# FMC_HPC_UFL_DEBUG_TP_SMA.net
KiCad netlist of a schematic drawn in Altium Designer
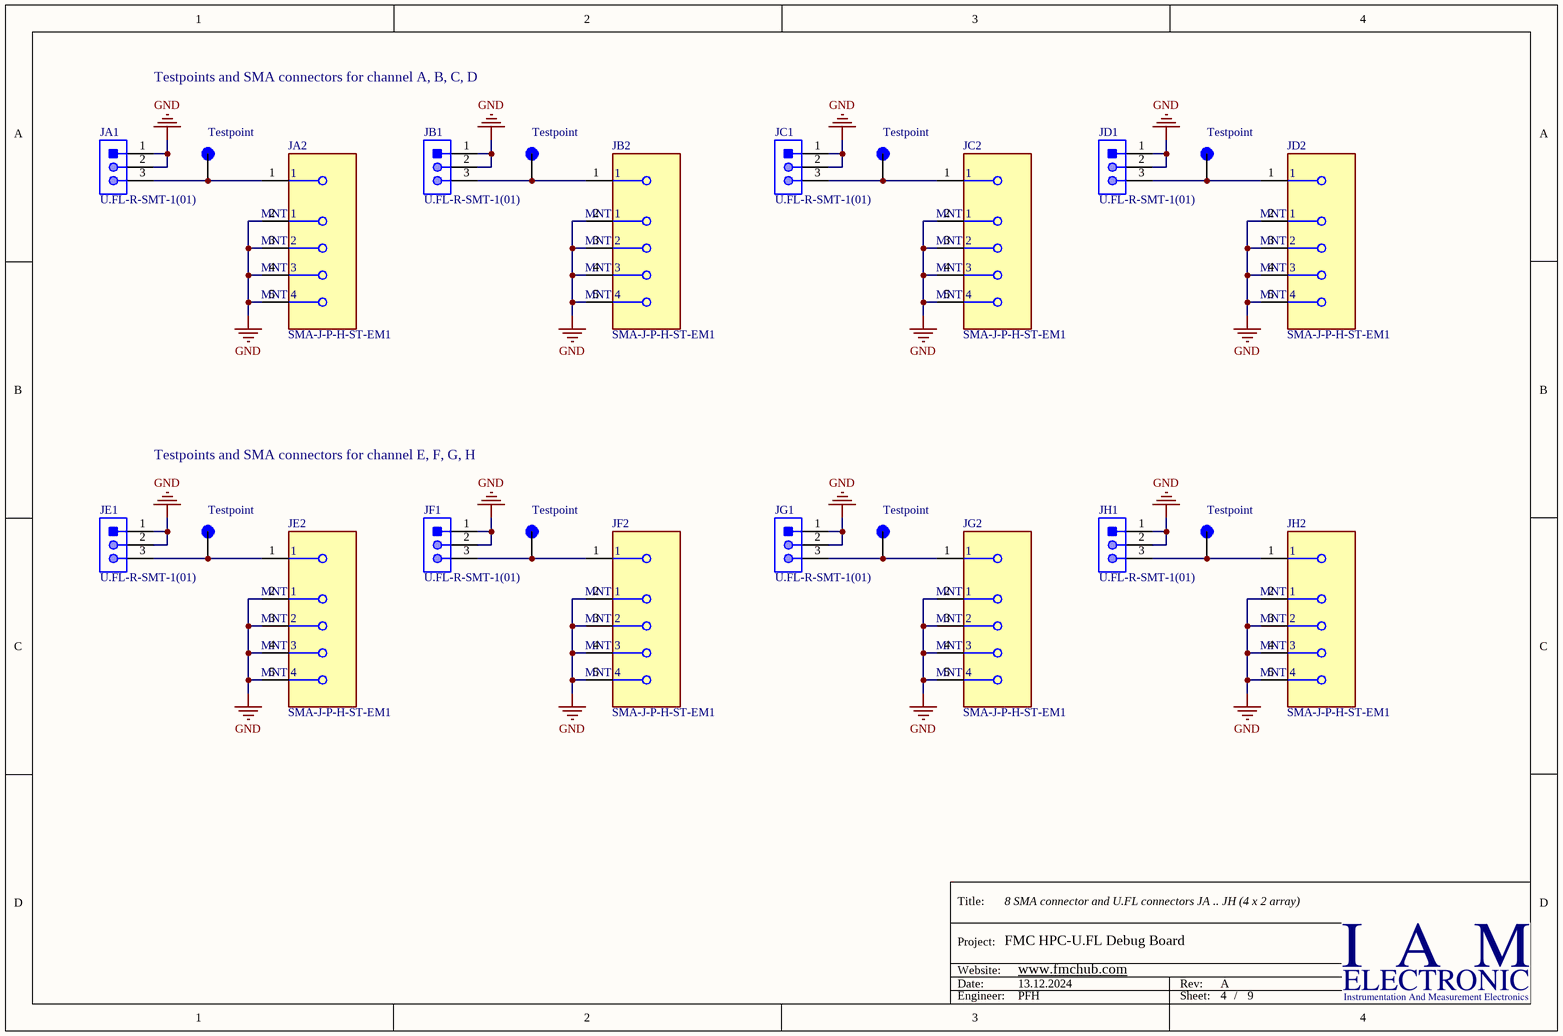
[diagram p0: FMC_HPC_UFL_DEBUG_TP_SMA.SchDoc]

(export (version "E")
  (design (tool "Eeschema 10.0.6"))
  (components
    (comp (ref "JA1")
      (value "U.FL-R-SMT-1(01)")
      (footprint "HRS-U.FL-R-SMT-3_V")
      (description "Ultra Small Coaxial Connector, 6 GHz, -40 to 90 degC, 3-Pin SMD, RoHS, Bulk")
      (fields (field (name "MANUFACTURER") "Hirose Electric"))
      (libsource (lib "Altium Content Vault") (part "CN-1P-M-R3"))
    )
    (comp (ref "JA2")
      (value "SMA-J-P-H-ST-EM1")
      (footprint "FP-SMA-J-P-H-ST-EM1-MFG")
      (description "CONN SMA JACK STR 50OHM EDGE MNT")
      (fields (field (name "MANUFACTURER") "Samtec"))
      (libsource (lib "Altium Content Vault") (part "c65b8a639cdaef1819ea20b5466f8fa"))
    )
    (comp (ref "JB1")
      (value "U.FL-R-SMT-1(01)")
      (footprint "HRS-U.FL-R-SMT-3_V")
      (description "Ultra Small Coaxial Connector, 6 GHz, -40 to 90 degC, 3-Pin SMD, RoHS, Bulk")
      (fields (field (name "MANUFACTURER") "Hirose Electric"))
      (libsource (lib "Altium Content Vault") (part "CN-1P-M-R3"))
    )
    (comp (ref "JB2")
      (value "SMA-J-P-H-ST-EM1")
      (footprint "FP-SMA-J-P-H-ST-EM1-MFG")
      (description "CONN SMA JACK STR 50OHM EDGE MNT")
      (fields (field (name "MANUFACTURER") "Samtec"))
      (libsource (lib "Altium Content Vault") (part "c65b8a639cdaef1819ea20b5466f8fa"))
    )
    (comp (ref "JC1")
      (value "U.FL-R-SMT-1(01)")
      (footprint "HRS-U.FL-R-SMT-3_V")
      (description "Ultra Small Coaxial Connector, 6 GHz, -40 to 90 degC, 3-Pin SMD, RoHS, Bulk")
      (fields (field (name "MANUFACTURER") "Hirose Electric"))
      (libsource (lib "Altium Content Vault") (part "CN-1P-M-R3"))
    )
    (comp (ref "JC2")
      (value "SMA-J-P-H-ST-EM1")
      (footprint "FP-SMA-J-P-H-ST-EM1-MFG")
      (description "CONN SMA JACK STR 50OHM EDGE MNT")
      (fields (field (name "MANUFACTURER") "Samtec"))
      (libsource (lib "Altium Content Vault") (part "c65b8a639cdaef1819ea20b5466f8fa"))
    )
    (comp (ref "JD1")
      (value "U.FL-R-SMT-1(01)")
      (footprint "HRS-U.FL-R-SMT-3_V")
      (description "Ultra Small Coaxial Connector, 6 GHz, -40 to 90 degC, 3-Pin SMD, RoHS, Bulk")
      (fields (field (name "MANUFACTURER") "Hirose Electric"))
      (libsource (lib "Altium Content Vault") (part "CN-1P-M-R3"))
    )
    (comp (ref "JD2")
      (value "SMA-J-P-H-ST-EM1")
      (footprint "FP-SMA-J-P-H-ST-EM1-MFG")
      (description "CONN SMA JACK STR 50OHM EDGE MNT")
      (fields (field (name "MANUFACTURER") "Samtec"))
      (libsource (lib "Altium Content Vault") (part "c65b8a639cdaef1819ea20b5466f8fa"))
    )
    (comp (ref "JE1")
      (value "U.FL-R-SMT-1(01)")
      (footprint "HRS-U.FL-R-SMT-3_V")
      (description "Ultra Small Coaxial Connector, 6 GHz, -40 to 90 degC, 3-Pin SMD, RoHS, Bulk")
      (fields (field (name "MANUFACTURER") "Hirose Electric"))
      (libsource (lib "Altium Content Vault") (part "CN-1P-M-R3"))
    )
    (comp (ref "JE2")
      (value "SMA-J-P-H-ST-EM1")
      (footprint "FP-SMA-J-P-H-ST-EM1-MFG")
      (description "CONN SMA JACK STR 50OHM EDGE MNT")
      (fields (field (name "MANUFACTURER") "Samtec"))
      (libsource (lib "Altium Content Vault") (part "c65b8a639cdaef1819ea20b5466f8fa"))
    )
    (comp (ref "JF1")
      (value "U.FL-R-SMT-1(01)")
      (footprint "HRS-U.FL-R-SMT-3_V")
      (description "Ultra Small Coaxial Connector, 6 GHz, -40 to 90 degC, 3-Pin SMD, RoHS, Bulk")
      (fields (field (name "MANUFACTURER") "Hirose Electric"))
      (libsource (lib "Altium Content Vault") (part "CN-1P-M-R3"))
    )
    (comp (ref "JF2")
      (value "SMA-J-P-H-ST-EM1")
      (footprint "FP-SMA-J-P-H-ST-EM1-MFG")
      (description "CONN SMA JACK STR 50OHM EDGE MNT")
      (fields (field (name "MANUFACTURER") "Samtec"))
      (libsource (lib "Altium Content Vault") (part "c65b8a639cdaef1819ea20b5466f8fa"))
    )
    (comp (ref "JG1")
      (value "U.FL-R-SMT-1(01)")
      (footprint "HRS-U.FL-R-SMT-3_V")
      (description "Ultra Small Coaxial Connector, 6 GHz, -40 to 90 degC, 3-Pin SMD, RoHS, Bulk")
      (fields (field (name "MANUFACTURER") "Hirose Electric"))
      (libsource (lib "Altium Content Vault") (part "CN-1P-M-R3"))
    )
    (comp (ref "JG2")
      (value "SMA-J-P-H-ST-EM1")
      (footprint "FP-SMA-J-P-H-ST-EM1-MFG")
      (description "CONN SMA JACK STR 50OHM EDGE MNT")
      (fields (field (name "MANUFACTURER") "Samtec"))
      (libsource (lib "Altium Content Vault") (part "c65b8a639cdaef1819ea20b5466f8fa"))
    )
    (comp (ref "JH1")
      (value "U.FL-R-SMT-1(01)")
      (footprint "HRS-U.FL-R-SMT-3_V")
      (description "Ultra Small Coaxial Connector, 6 GHz, -40 to 90 degC, 3-Pin SMD, RoHS, Bulk")
      (fields (field (name "MANUFACTURER") "Hirose Electric"))
      (libsource (lib "Altium Content Vault") (part "CN-1P-M-R3"))
    )
    (comp (ref "JH2")
      (value "SMA-J-P-H-ST-EM1")
      (footprint "FP-SMA-J-P-H-ST-EM1-MFG")
      (description "CONN SMA JACK STR 50OHM EDGE MNT")
      (fields (field (name "MANUFACTURER") "Samtec"))
      (libsource (lib "Altium Content Vault") (part "c65b8a639cdaef1819ea20b5466f8fa"))
    )
    (comp (ref "TPA1")
      (value "Testpoint")
      (footprint "KEYSTONE_5095")
      (description "PC TEST POINT COMPACT")
      (fields (field (name "MANUFACTURER") "Keystone Electronics") (field (name "PART") "5095"))
      (libsource (lib "KEYSTONE_5095") (part "5095"))
    )
    (comp (ref "TPB1")
      (value "Testpoint")
      (footprint "KEYSTONE_5095")
      (description "PC TEST POINT COMPACT")
      (fields (field (name "MANUFACTURER") "Keystone Electronics") (field (name "PART") "5095"))
      (libsource (lib "KEYSTONE_5095") (part "5095"))
    )
    (comp (ref "TPC1")
      (value "Testpoint")
      (footprint "KEYSTONE_5095")
      (description "PC TEST POINT COMPACT")
      (fields (field (name "MANUFACTURER") "Keystone Electronics") (field (name "PART") "5095"))
      (libsource (lib "KEYSTONE_5095") (part "5095"))
    )
    (comp (ref "TPD1")
      (value "Testpoint")
      (footprint "KEYSTONE_5095")
      (description "PC TEST POINT COMPACT")
      (fields (field (name "MANUFACTURER") "Keystone Electronics") (field (name "PART") "5095"))
      (libsource (lib "KEYSTONE_5095") (part "5095"))
    )
    (comp (ref "TPE1")
      (value "Testpoint")
      (footprint "KEYSTONE_5095")
      (description "PC TEST POINT COMPACT")
      (fields (field (name "MANUFACTURER") "Keystone Electronics") (field (name "PART") "5095"))
      (libsource (lib "KEYSTONE_5095") (part "5095"))
    )
    (comp (ref "TPF1")
      (value "Testpoint")
      (footprint "KEYSTONE_5095")
      (description "PC TEST POINT COMPACT")
      (fields (field (name "MANUFACTURER") "Keystone Electronics") (field (name "PART") "5095"))
      (libsource (lib "KEYSTONE_5095") (part "5095"))
    )
    (comp (ref "TPG2")
      (value "Testpoint")
      (footprint "KEYSTONE_5095")
      (description "PC TEST POINT COMPACT")
      (fields (field (name "MANUFACTURER") "Keystone Electronics") (field (name "PART") "5095"))
      (libsource (lib "KEYSTONE_5095") (part "5095"))
    )
    (comp (ref "TPH1")
      (value "Testpoint")
      (footprint "KEYSTONE_5095")
      (description "PC TEST POINT COMPACT")
      (fields (field (name "MANUFACTURER") "Keystone Electronics") (field (name "PART") "5095"))
      (libsource (lib "KEYSTONE_5095") (part "5095"))
    )
  )
  (nets
    (net (code "1") (name "GND") (class "Default")
      (node (ref "JA1") (pin "1") (pinfunction "1_1") (pintype "passive"))
      (node (ref "JA1") (pin "2") (pinfunction "2_2") (pintype "passive"))
      (node (ref "JA2") (pin "2") (pinfunction "MNT_1_2") (pintype "passive"))
      (node (ref "JA2") (pin "3") (pinfunction "MNT_2_3") (pintype "passive"))
      (node (ref "JA2") (pin "4") (pinfunction "MNT_3_4") (pintype "passive"))
      (node (ref "JA2") (pin "5") (pinfunction "MNT_4_5") (pintype "passive"))
      (node (ref "JB1") (pin "1") (pinfunction "1_1") (pintype "passive"))
      (node (ref "JB1") (pin "2") (pinfunction "2_2") (pintype "passive"))
      (node (ref "JB2") (pin "2") (pinfunction "MNT_1_2") (pintype "passive"))
      (node (ref "JB2") (pin "3") (pinfunction "MNT_2_3") (pintype "passive"))
      (node (ref "JB2") (pin "4") (pinfunction "MNT_3_4") (pintype "passive"))
      (node (ref "JB2") (pin "5") (pinfunction "MNT_4_5") (pintype "passive"))
      (node (ref "JC1") (pin "1") (pinfunction "1_1") (pintype "passive"))
      (node (ref "JC1") (pin "2") (pinfunction "2_2") (pintype "passive"))
      (node (ref "JC2") (pin "2") (pinfunction "MNT_1_2") (pintype "passive"))
      (node (ref "JC2") (pin "3") (pinfunction "MNT_2_3") (pintype "passive"))
      (node (ref "JC2") (pin "4") (pinfunction "MNT_3_4") (pintype "passive"))
      (node (ref "JC2") (pin "5") (pinfunction "MNT_4_5") (pintype "passive"))
      (node (ref "JD1") (pin "1") (pinfunction "1_1") (pintype "passive"))
      (node (ref "JD1") (pin "2") (pinfunction "2_2") (pintype "passive"))
      (node (ref "JD2") (pin "2") (pinfunction "MNT_1_2") (pintype "passive"))
      (node (ref "JD2") (pin "3") (pinfunction "MNT_2_3") (pintype "passive"))
      (node (ref "JD2") (pin "4") (pinfunction "MNT_3_4") (pintype "passive"))
      (node (ref "JD2") (pin "5") (pinfunction "MNT_4_5") (pintype "passive"))
      (node (ref "JE1") (pin "1") (pinfunction "1_1") (pintype "passive"))
      (node (ref "JE1") (pin "2") (pinfunction "2_2") (pintype "passive"))
      (node (ref "JE2") (pin "2") (pinfunction "MNT_1_2") (pintype "passive"))
      (node (ref "JE2") (pin "3") (pinfunction "MNT_2_3") (pintype "passive"))
      (node (ref "JE2") (pin "4") (pinfunction "MNT_3_4") (pintype "passive"))
      (node (ref "JE2") (pin "5") (pinfunction "MNT_4_5") (pintype "passive"))
      (node (ref "JF1") (pin "1") (pinfunction "1_1") (pintype "passive"))
      (node (ref "JF1") (pin "2") (pinfunction "2_2") (pintype "passive"))
      (node (ref "JF2") (pin "2") (pinfunction "MNT_1_2") (pintype "passive"))
      (node (ref "JF2") (pin "3") (pinfunction "MNT_2_3") (pintype "passive"))
      (node (ref "JF2") (pin "4") (pinfunction "MNT_3_4") (pintype "passive"))
      (node (ref "JF2") (pin "5") (pinfunction "MNT_4_5") (pintype "passive"))
      (node (ref "JG1") (pin "1") (pinfunction "1_1") (pintype "passive"))
      (node (ref "JG1") (pin "2") (pinfunction "2_2") (pintype "passive"))
      (node (ref "JG2") (pin "2") (pinfunction "MNT_1_2") (pintype "passive"))
      (node (ref "JG2") (pin "3") (pinfunction "MNT_2_3") (pintype "passive"))
      (node (ref "JG2") (pin "4") (pinfunction "MNT_3_4") (pintype "passive"))
      (node (ref "JG2") (pin "5") (pinfunction "MNT_4_5") (pintype "passive"))
      (node (ref "JH1") (pin "1") (pinfunction "1_1") (pintype "passive"))
      (node (ref "JH1") (pin "2") (pinfunction "2_2") (pintype "passive"))
      (node (ref "JH2") (pin "2") (pinfunction "MNT_1_2") (pintype "passive"))
      (node (ref "JH2") (pin "3") (pinfunction "MNT_2_3") (pintype "passive"))
      (node (ref "JH2") (pin "4") (pinfunction "MNT_3_4") (pintype "passive"))
      (node (ref "JH2") (pin "5") (pinfunction "MNT_4_5") (pintype "passive"))
    )
    (net (code "2") (name "Net-(TPA1-TP)") (class "Default")
      (node (ref "JA1") (pin "3") (pinfunction "3_3") (pintype "passive"))
      (node (ref "JA2") (pin "1") (pinfunction "1_1") (pintype "passive"))
      (node (ref "TPA1") (pin "1") (pinfunction "TP_1") (pintype "passive"))
    )
    (net (code "3") (name "Net-(TPB1-TP)") (class "Default")
      (node (ref "JB1") (pin "3") (pinfunction "3_3") (pintype "passive"))
      (node (ref "JB2") (pin "1") (pinfunction "1_1") (pintype "passive"))
      (node (ref "TPB1") (pin "1") (pinfunction "TP_1") (pintype "passive"))
    )
    (net (code "4") (name "Net-(TPC1-TP)") (class "Default")
      (node (ref "JC1") (pin "3") (pinfunction "3_3") (pintype "passive"))
      (node (ref "JC2") (pin "1") (pinfunction "1_1") (pintype "passive"))
      (node (ref "TPC1") (pin "1") (pinfunction "TP_1") (pintype "passive"))
    )
    (net (code "5") (name "Net-(TPD1-TP)") (class "Default")
      (node (ref "JD1") (pin "3") (pinfunction "3_3") (pintype "passive"))
      (node (ref "JD2") (pin "1") (pinfunction "1_1") (pintype "passive"))
      (node (ref "TPD1") (pin "1") (pinfunction "TP_1") (pintype "passive"))
    )
    (net (code "6") (name "Net-(TPE1-TP)") (class "Default")
      (node (ref "JE1") (pin "3") (pinfunction "3_3") (pintype "passive"))
      (node (ref "JE2") (pin "1") (pinfunction "1_1") (pintype "passive"))
      (node (ref "TPE1") (pin "1") (pinfunction "TP_1") (pintype "passive"))
    )
    (net (code "7") (name "Net-(TPF1-TP)") (class "Default")
      (node (ref "JF1") (pin "3") (pinfunction "3_3") (pintype "passive"))
      (node (ref "JF2") (pin "1") (pinfunction "1_1") (pintype "passive"))
      (node (ref "TPF1") (pin "1") (pinfunction "TP_1") (pintype "passive"))
    )
    (net (code "8") (name "Net-(TPG2-TP)") (class "Default")
      (node (ref "JG1") (pin "3") (pinfunction "3_3") (pintype "passive"))
      (node (ref "JG2") (pin "1") (pinfunction "1_1") (pintype "passive"))
      (node (ref "TPG2") (pin "1") (pinfunction "TP_1") (pintype "passive"))
    )
    (net (code "9") (name "Net-(TPH1-TP)") (class "Default")
      (node (ref "JH1") (pin "3") (pinfunction "3_3") (pintype "passive"))
      (node (ref "JH2") (pin "1") (pinfunction "1_1") (pintype "passive"))
      (node (ref "TPH1") (pin "1") (pinfunction "TP_1") (pintype "passive"))
    )
  )
)
